# module.net
KiCad netlist of a schematic drawn in EAGLE
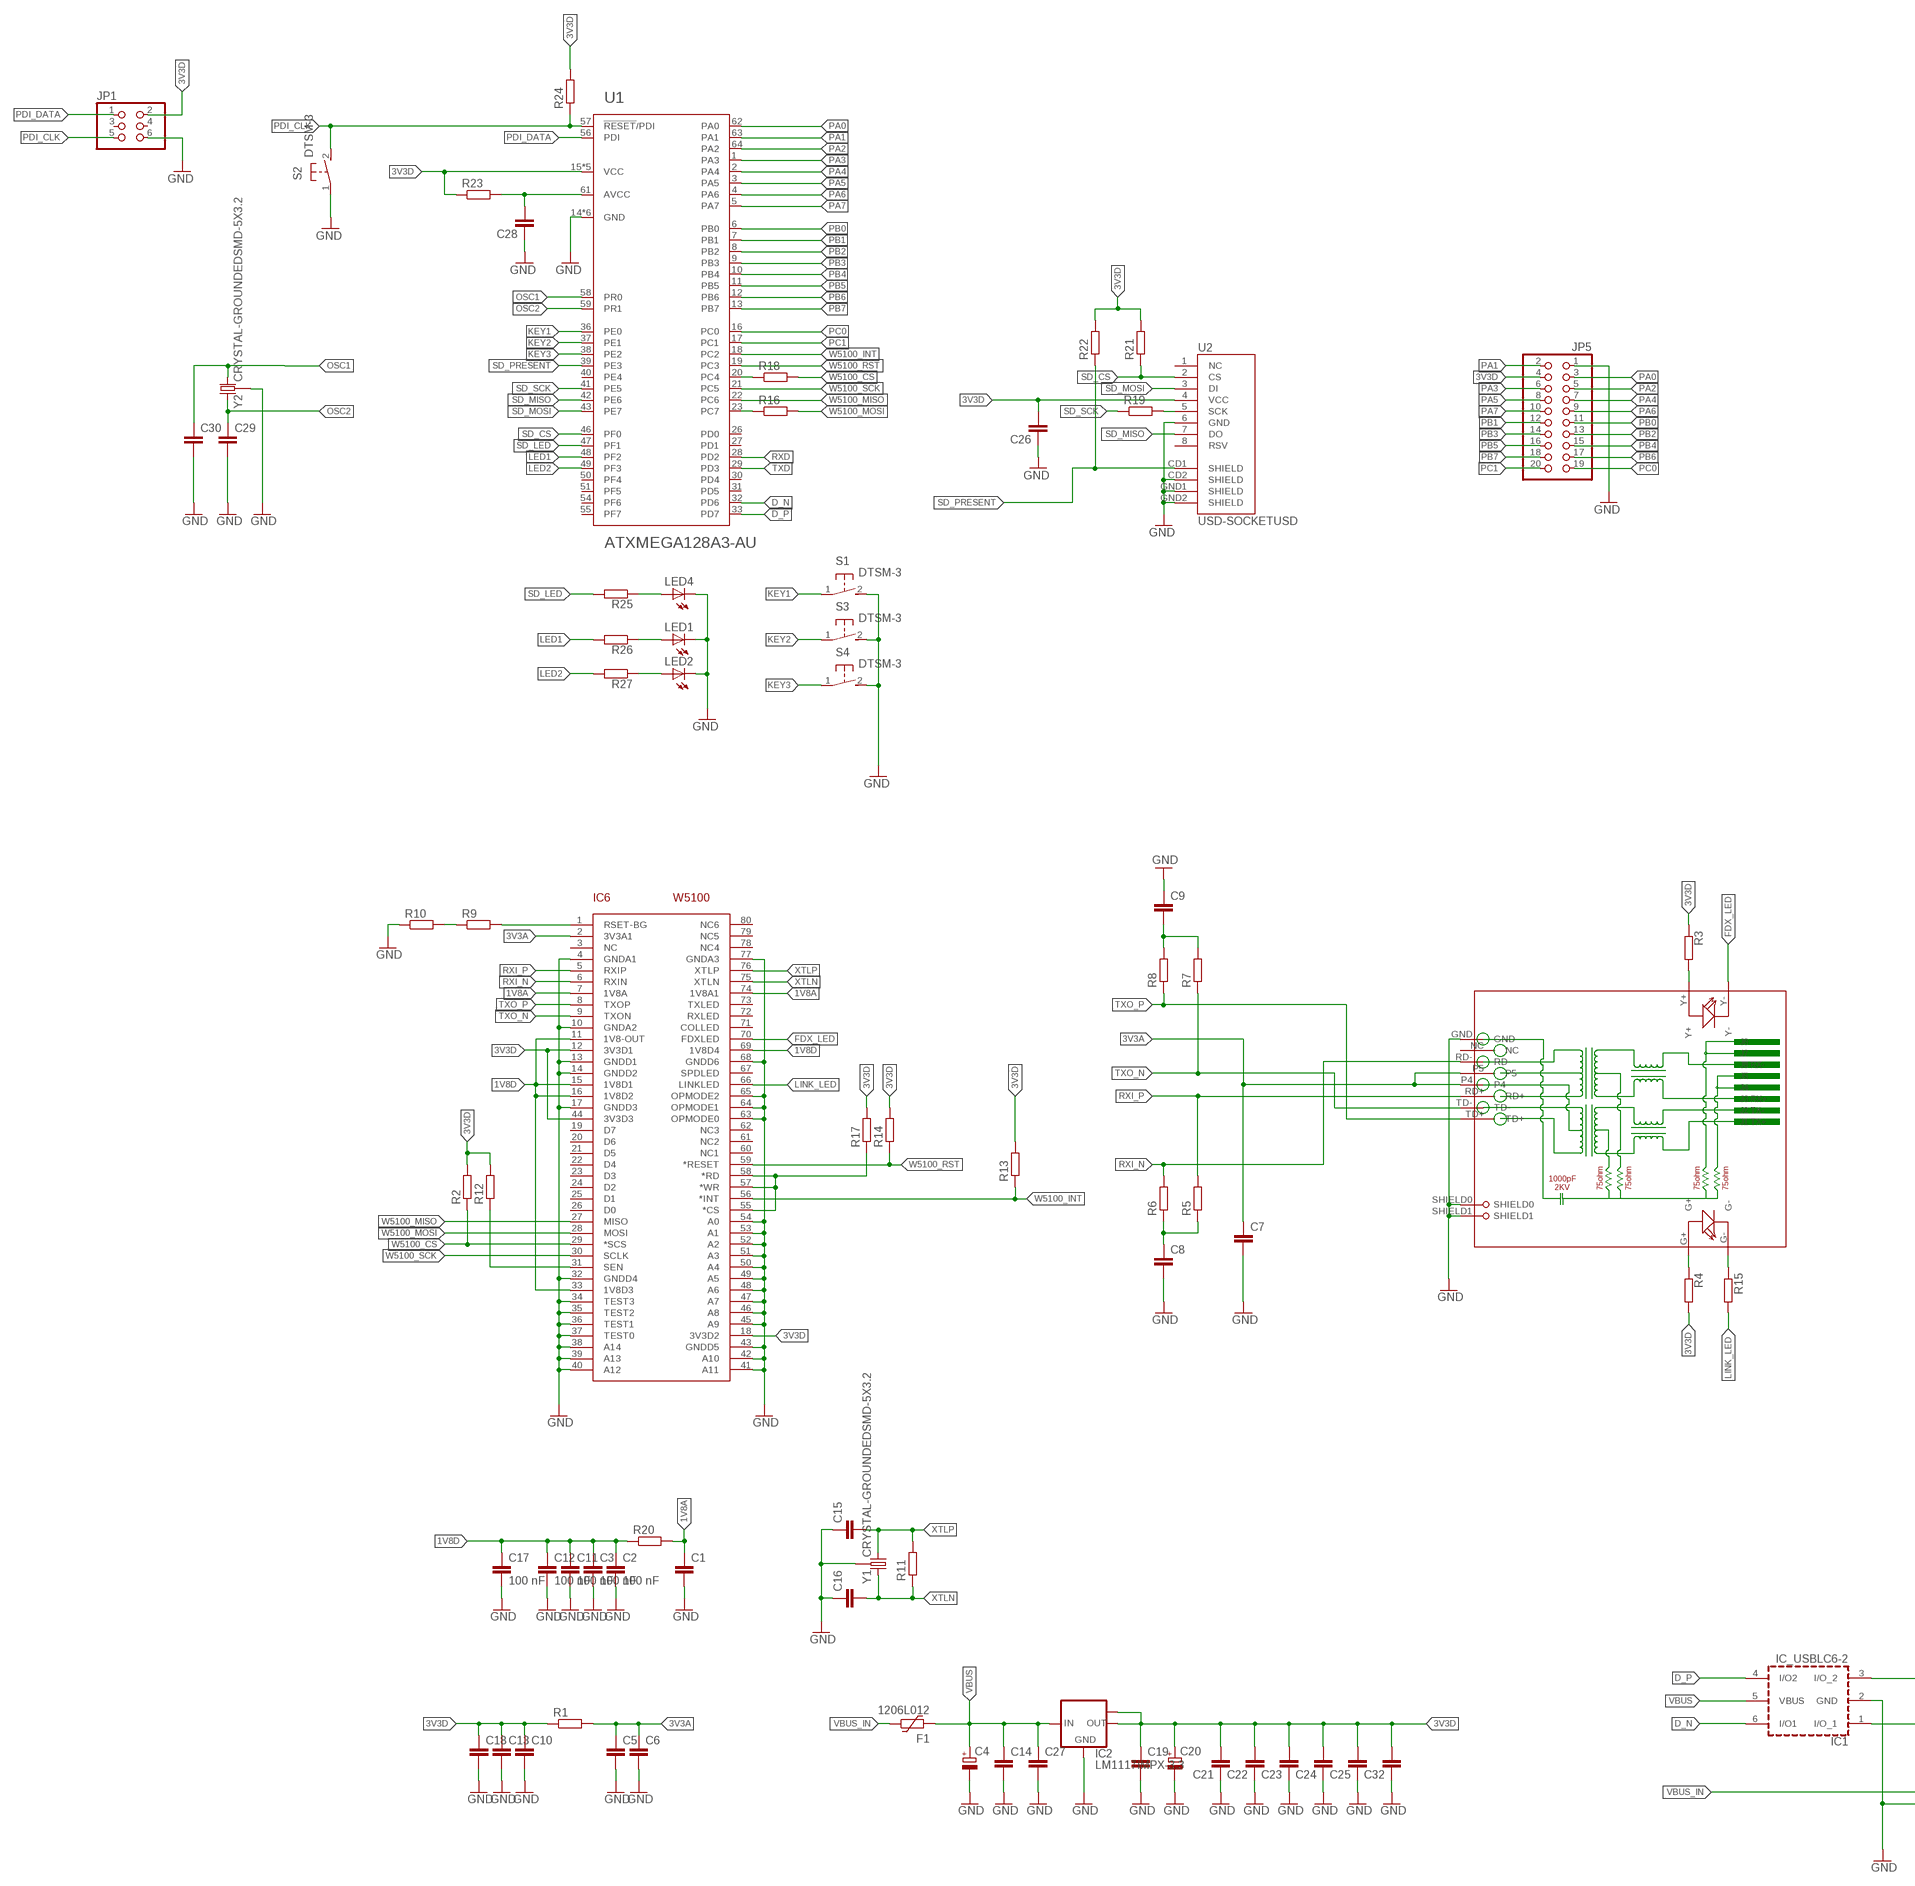
[diagram p0: schematic, sheet 1, part 1 of 2]
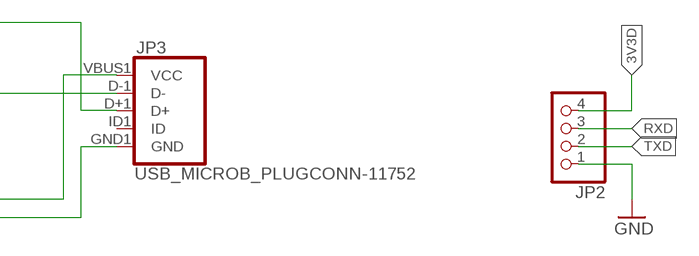
[diagram p1: schematic, sheet 1, part 2 of 2]

(export (version "E")
  (design (tool "Eeschema 10.0.6"))
  (components
    (comp (ref "C1")
      (value "C-EUC0603")
      (footprint "eagle-import:C0603")
      (libsource (lib "eagle-import") (part "C-EUC0603"))
    )
    (comp (ref "C2")
      (value "100 nF")
      (footprint "eagle-import:C0402")
      (libsource (lib "eagle-import") (part "C-EUC0402"))
    )
    (comp (ref "C3")
      (value "100 nF")
      (footprint "eagle-import:C0603")
      (libsource (lib "eagle-import") (part "C-EUC0603"))
    )
    (comp (ref "C4")
      (value "CPOL-EUSMCB")
      (footprint "eagle-import:SMC_B")
      (libsource (lib "eagle-import") (part "CPOL-EUSMCB"))
    )
    (comp (ref "C5")
      (value "C-EUC0603")
      (footprint "eagle-import:C0603")
      (libsource (lib "eagle-import") (part "C-EUC0603"))
    )
    (comp (ref "C6")
      (value "C-EUC0603")
      (footprint "eagle-import:C0603")
      (libsource (lib "eagle-import") (part "C-EUC0603"))
    )
    (comp (ref "C7")
      (value "C-EUC0603")
      (footprint "eagle-import:C0603")
      (libsource (lib "eagle-import") (part "C-EUC0603"))
    )
    (comp (ref "C8")
      (value "C-EUC0603")
      (footprint "eagle-import:C0603")
      (libsource (lib "eagle-import") (part "C-EUC0603"))
    )
    (comp (ref "C9")
      (value "C-EUC0603")
      (footprint "eagle-import:C0603")
      (libsource (lib "eagle-import") (part "C-EUC0603"))
    )
    (comp (ref "C10")
      (value "C-EUC0402")
      (footprint "eagle-import:C0402")
      (libsource (lib "eagle-import") (part "C-EUC0402"))
    )
    (comp (ref "C11")
      (value "100 nF")
      (footprint "eagle-import:C0402")
      (libsource (lib "eagle-import") (part "C-EUC0402"))
    )
    (comp (ref "C12")
      (value "100 nF")
      (footprint "eagle-import:C0402")
      (libsource (lib "eagle-import") (part "C-EUC0402"))
    )
    (comp (ref "C13")
      (value "C-EUC0402")
      (footprint "eagle-import:C0402")
      (libsource (lib "eagle-import") (part "C-EUC0402"))
    )
    (comp (ref "C14")
      (value "C-EUC0603")
      (footprint "eagle-import:C0603")
      (libsource (lib "eagle-import") (part "C-EUC0603"))
    )
    (comp (ref "C15")
      (value "C-EUC0603")
      (footprint "eagle-import:C0603")
      (libsource (lib "eagle-import") (part "C-EUC0603"))
    )
    (comp (ref "C16")
      (value "C-EUC0603")
      (footprint "eagle-import:C0603")
      (libsource (lib "eagle-import") (part "C-EUC0603"))
    )
    (comp (ref "C17")
      (value "100 nF")
      (footprint "eagle-import:C0402")
      (libsource (lib "eagle-import") (part "C-EUC0402"))
    )
    (comp (ref "C18")
      (value "C-EUC0402")
      (footprint "eagle-import:C0402")
      (libsource (lib "eagle-import") (part "C-EUC0402"))
    )
    (comp (ref "C19")
      (value "C-EUC0603")
      (footprint "eagle-import:C0603")
      (libsource (lib "eagle-import") (part "C-EUC0603"))
    )
    (comp (ref "C20")
      (value "CPOL-EUSMCB")
      (footprint "eagle-import:SMC_B")
      (libsource (lib "eagle-import") (part "CPOL-EUSMCB"))
    )
    (comp (ref "C21")
      (value "C-EUC0402")
      (footprint "eagle-import:C0402")
      (libsource (lib "eagle-import") (part "C-EUC0402"))
    )
    (comp (ref "C22")
      (value "C-EUC0402")
      (footprint "eagle-import:C0402")
      (libsource (lib "eagle-import") (part "C-EUC0402"))
    )
    (comp (ref "C23")
      (value "C-EUC0402")
      (footprint "eagle-import:C0402")
      (libsource (lib "eagle-import") (part "C-EUC0402"))
    )
    (comp (ref "C24")
      (value "C-EUC0402")
      (footprint "eagle-import:C0402")
      (libsource (lib "eagle-import") (part "C-EUC0402"))
    )
    (comp (ref "C25")
      (value "C-EUC0402")
      (footprint "eagle-import:C0402")
      (libsource (lib "eagle-import") (part "C-EUC0402"))
    )
    (comp (ref "C26")
      (value "C-EUC0603")
      (footprint "eagle-import:C0603")
      (libsource (lib "eagle-import") (part "C-EUC0603"))
    )
    (comp (ref "C27")
      (value "C-EUC0603")
      (footprint "eagle-import:C0603")
      (libsource (lib "eagle-import") (part "C-EUC0603"))
    )
    (comp (ref "C28")
      (value "C-EUC0402")
      (footprint "eagle-import:C0402")
      (libsource (lib "eagle-import") (part "C-EUC0402"))
    )
    (comp (ref "C29")
      (value "C-EUC0603")
      (footprint "eagle-import:C0603")
      (libsource (lib "eagle-import") (part "C-EUC0603"))
    )
    (comp (ref "C30")
      (value "C-EUC0603")
      (footprint "eagle-import:C0603")
      (libsource (lib "eagle-import") (part "C-EUC0603"))
    )
    (comp (ref "C32")
      (value "C-EUC0603")
      (footprint "eagle-import:C0603")
      (libsource (lib "eagle-import") (part "C-EUC0603"))
    )
    (comp (ref "F1")
      (value "1206L012")
      (footprint "eagle-import:1206L")
      (fields (field (name "MF") "Littelfuse"))
      (libsource (lib "eagle-import") (part "?1206L012"))
    )
    (comp (ref "IC1")
      (value "IC_USBLC6-2")
      (footprint "eagle-import:SOT-23-6L")
      (libsource (lib "eagle-import") (part "IC_USBLC6-2"))
    )
    (comp (ref "IC2")
      (value "LM1117IMPX-3.3")
      (footprint "eagle-import:SOT223")
      (libsource (lib "eagle-import") (part "LM1117IMPX-3.3"))
    )
    (comp (ref "IC6")
      (value "W5100")
      (footprint "eagle-import:SQFP-S-10X10-80")
      (libsource (lib "eagle-import") (part "W5100"))
    )
    (comp (ref "JP1")
      (value "PINHD-2X3")
      (footprint "eagle-import:2X03")
      (libsource (lib "eagle-import") (part "PINHD-2X3"))
    )
    (comp (ref "JP2")
      (value "PINHD-1X4")
      (footprint "eagle-import:1X04")
      (libsource (lib "eagle-import") (part "PINHD-1X4"))
    )
    (comp (ref "JP3")
      (value "USB_MICROB_PLUGCONN-11752")
      (footprint "eagle-import:USB-B-MICRO-SMD_V03")
      (libsource (lib "eagle-import") (part "USB_MICROB_PLUGCONN-11752"))
    )
    (comp (ref "JP5")
      (value "PINHD-2X10_2.54-SMD")
      (footprint "eagle-import:2X10SMD")
      (libsource (lib "eagle-import") (part "PINHD-2X10_2.54-SMD"))
    )
    (comp (ref "LED1")
      (value "LEDCHIPLED_0805")
      (footprint "eagle-import:CHIPLED_0805")
      (libsource (lib "eagle-import") (part "LEDCHIPLED_0805"))
    )
    (comp (ref "LED2")
      (value "LEDCHIPLED_0805")
      (footprint "eagle-import:CHIPLED_0805")
      (libsource (lib "eagle-import") (part "LEDCHIPLED_0805"))
    )
    (comp (ref "LED4")
      (value "LEDCHIPLED_0805")
      (footprint "eagle-import:CHIPLED_0805")
      (libsource (lib "eagle-import") (part "LEDCHIPLED_0805"))
    )
    (comp (ref "R1")
      (value "R-EU_R0805")
      (footprint "eagle-import:R0805")
      (libsource (lib "eagle-import") (part "R-EU_R0805"))
    )
    (comp (ref "R2")
      (value "R-EU_R0603")
      (footprint "eagle-import:R0603")
      (libsource (lib "eagle-import") (part "R-EU_R0603"))
    )
    (comp (ref "R3")
      (value "R-EU_R0603")
      (footprint "eagle-import:R0603")
      (libsource (lib "eagle-import") (part "R-EU_R0603"))
    )
    (comp (ref "R4")
      (value "R-EU_R0603")
      (footprint "eagle-import:R0603")
      (libsource (lib "eagle-import") (part "R-EU_R0603"))
    )
    (comp (ref "R5")
      (value "R-EU_R0603")
      (footprint "eagle-import:R0603")
      (libsource (lib "eagle-import") (part "R-EU_R0603"))
    )
    (comp (ref "R6")
      (value "R-EU_R0603")
      (footprint "eagle-import:R0603")
      (libsource (lib "eagle-import") (part "R-EU_R0603"))
    )
    (comp (ref "R7")
      (value "R-EU_R0603")
      (footprint "eagle-import:R0603")
      (libsource (lib "eagle-import") (part "R-EU_R0603"))
    )
    (comp (ref "R8")
      (value "R-EU_R0603")
      (footprint "eagle-import:R0603")
      (libsource (lib "eagle-import") (part "R-EU_R0603"))
    )
    (comp (ref "R9")
      (value "R-EU_R0603")
      (footprint "eagle-import:R0603")
      (libsource (lib "eagle-import") (part "R-EU_R0603"))
    )
    (comp (ref "R10")
      (value "R-EU_R0603")
      (footprint "eagle-import:R0603")
      (libsource (lib "eagle-import") (part "R-EU_R0603"))
    )
    (comp (ref "R11")
      (value "R-EU_R0603")
      (footprint "eagle-import:R0603")
      (libsource (lib "eagle-import") (part "R-EU_R0603"))
    )
    (comp (ref "R12")
      (value "R-EU_R0402")
      (footprint "eagle-import:R0402")
      (libsource (lib "eagle-import") (part "R-EU_R0402"))
    )
    (comp (ref "R13")
      (value "R-EU_R0603")
      (footprint "eagle-import:R0603")
      (libsource (lib "eagle-import") (part "R-EU_R0603"))
    )
    (comp (ref "R14")
      (value "R-EU_R0402")
      (footprint "eagle-import:R0402")
      (libsource (lib "eagle-import") (part "R-EU_R0402"))
    )
    (comp (ref "R15")
      (value "R-EU_R0603")
      (footprint "eagle-import:R0603")
      (libsource (lib "eagle-import") (part "R-EU_R0603"))
    )
    (comp (ref "R16")
      (value "R-EU_R0603")
      (footprint "eagle-import:R0603")
      (libsource (lib "eagle-import") (part "R-EU_R0603"))
    )
    (comp (ref "R17")
      (value "R-EU_R0603")
      (footprint "eagle-import:R0603")
      (libsource (lib "eagle-import") (part "R-EU_R0603"))
    )
    (comp (ref "R18")
      (value "R-EU_R0603")
      (footprint "eagle-import:R0603")
      (libsource (lib "eagle-import") (part "R-EU_R0603"))
    )
    (comp (ref "R19")
      (value "R-EU_R0603")
      (footprint "eagle-import:R0603")
      (libsource (lib "eagle-import") (part "R-EU_R0603"))
    )
    (comp (ref "R20")
      (value "R-EU_R0805")
      (footprint "eagle-import:R0805")
      (libsource (lib "eagle-import") (part "R-EU_R0805"))
    )
    (comp (ref "R21")
      (value "R-EU_R0603")
      (footprint "eagle-import:R0603")
      (libsource (lib "eagle-import") (part "R-EU_R0603"))
    )
    (comp (ref "R22")
      (value "R-EU_R0603")
      (footprint "eagle-import:R0603")
      (libsource (lib "eagle-import") (part "R-EU_R0603"))
    )
    (comp (ref "R23")
      (value "R-EU_R0805")
      (footprint "eagle-import:R0805")
      (libsource (lib "eagle-import") (part "R-EU_R0805"))
    )
    (comp (ref "R24")
      (value "R-EU_R0603")
      (footprint "eagle-import:R0603")
      (libsource (lib "eagle-import") (part "R-EU_R0603"))
    )
    (comp (ref "R25")
      (value "R-EU_R0603")
      (footprint "eagle-import:R0603")
      (libsource (lib "eagle-import") (part "R-EU_R0603"))
    )
    (comp (ref "R26")
      (value "R-EU_R0603")
      (footprint "eagle-import:R0603")
      (libsource (lib "eagle-import") (part "R-EU_R0603"))
    )
    (comp (ref "R27")
      (value "R-EU_R0603")
      (footprint "eagle-import:R0603")
      (libsource (lib "eagle-import") (part "R-EU_R0603"))
    )
    (comp (ref "RJ1")
      (value "HR911105A")
      (footprint "eagle-import:HR911105A")
      (libsource (lib "eagle-import") (part "HR911105A"))
    )
    (comp (ref "S1")
      (value "DTSM-3")
      (footprint "eagle-import:DTSM-3")
      (libsource (lib "eagle-import") (part "DTSM-3"))
    )
    (comp (ref "S2")
      (value "DTSM-3")
      (footprint "eagle-import:DTSM-3")
      (libsource (lib "eagle-import") (part "DTSM-3"))
    )
    (comp (ref "S3")
      (value "DTSM-3")
      (footprint "eagle-import:DTSM-3")
      (libsource (lib "eagle-import") (part "DTSM-3"))
    )
    (comp (ref "S4")
      (value "DTSM-3")
      (footprint "eagle-import:DTSM-3")
      (libsource (lib "eagle-import") (part "DTSM-3"))
    )
    (comp (ref "U1")
      (value "ATXMEGA128A3-AU")
      (footprint "eagle-import:TQFP-64A-64")
      (libsource (lib "eagle-import") (part "ATXMEGA128A3-AU"))
    )
    (comp (ref "U2")
      (value "USD-SOCKETUSD")
      (footprint "eagle-import:USD-SOCKET-PP")
      (libsource (lib "eagle-import") (part "USD-SOCKETUSD"))
    )
    (comp (ref "Y1")
      (value "CRYSTAL-GROUNDEDSMD-5X3.2")
      (footprint "eagle-import:CRYSTAL-SMD-5X3.2-4PAD")
      (libsource (lib "eagle-import") (part "CRYSTAL-GROUNDEDSMD-5X3.2"))
    )
    (comp (ref "Y2")
      (value "CRYSTAL-GROUNDEDSMD-5X3.2")
      (footprint "eagle-import:CRYSTAL-SMD-5X3.2-4PAD")
      (libsource (lib "eagle-import") (part "CRYSTAL-GROUNDEDSMD-5X3.2"))
    )
  )
  (nets
    (net (code "1") (name "1V8A") (class "Default")
      (node (ref "C1") (pin "1") (pinfunction "1_1") (pintype "passive"))
      (node (ref "IC6") (pin "7") (pinfunction "1V8A_7") (pintype "power_in"))
      (node (ref "IC6") (pin "74") (pinfunction "1V8A1_74") (pintype "power_in"))
      (node (ref "R20") (pin "2") (pinfunction "2_2") (pintype "passive"))
    )
    (net (code "2") (name "1V8D") (class "Default")
      (node (ref "C11") (pin "1") (pinfunction "1_1") (pintype "passive"))
      (node (ref "C12") (pin "1") (pinfunction "1_1") (pintype "passive"))
      (node (ref "C17") (pin "1") (pinfunction "1_1") (pintype "passive"))
      (node (ref "C2") (pin "1") (pinfunction "1_1") (pintype "passive"))
      (node (ref "C3") (pin "1") (pinfunction "1_1") (pintype "passive"))
      (node (ref "IC6") (pin "11") (pinfunction "1V8-OUT_11") (pintype "power_in"))
      (node (ref "IC6") (pin "15") (pinfunction "1V8D1_15") (pintype "power_in"))
      (node (ref "IC6") (pin "16") (pinfunction "1V8D2_16") (pintype "power_in"))
      (node (ref "IC6") (pin "33") (pinfunction "1V8D3_33") (pintype "power_in"))
      (node (ref "IC6") (pin "69") (pinfunction "1V8D4_69") (pintype "power_in"))
      (node (ref "R20") (pin "1") (pinfunction "1_1") (pintype "passive"))
    )
    (net (code "3") (name "3V3A") (class "Default")
      (node (ref "C5") (pin "1") (pinfunction "1_1") (pintype "passive"))
      (node (ref "C6") (pin "1") (pinfunction "1_1") (pintype "passive"))
      (node (ref "C7") (pin "1") (pinfunction "1_1") (pintype "passive"))
      (node (ref "IC6") (pin "2") (pinfunction "3V3A1_2") (pintype "power_in"))
      (node (ref "R1") (pin "2") (pinfunction "2_2") (pintype "passive"))
      (node (ref "RJ1") (pin "P4") (pinfunction "P4_P4") (pintype "bidirectional"))
      (node (ref "RJ1") (pin "P5") (pinfunction "P5_P5") (pintype "bidirectional"))
    )
    (net (code "4") (name "3V3D") (class "Default")
      (node (ref "C10") (pin "1") (pinfunction "1_1") (pintype "passive"))
      (node (ref "C13") (pin "1") (pinfunction "1_1") (pintype "passive"))
      (node (ref "C18") (pin "1") (pinfunction "1_1") (pintype "passive"))
      (node (ref "C19") (pin "1") (pinfunction "1_1") (pintype "passive"))
      (node (ref "C20") (pin "+") (pinfunction "+_+") (pintype "passive"))
      (node (ref "C21") (pin "2") (pinfunction "2_2") (pintype "passive"))
      (node (ref "C22") (pin "2") (pinfunction "2_2") (pintype "passive"))
      (node (ref "C23") (pin "2") (pinfunction "2_2") (pintype "passive"))
      (node (ref "C24") (pin "2") (pinfunction "2_2") (pintype "passive"))
      (node (ref "C25") (pin "2") (pinfunction "2_2") (pintype "passive"))
      (node (ref "C26") (pin "2") (pinfunction "2_2") (pintype "passive"))
      (node (ref "C32") (pin "2") (pinfunction "2_2") (pintype "passive"))
      (node (ref "IC2") (pin "2") (pinfunction "OUT_2") (pintype "passive"))
      (node (ref "IC2") (pin "TAB") (pinfunction "OUT1_TAB") (pintype "passive"))
      (node (ref "IC6") (pin "12") (pinfunction "3V3D1_12") (pintype "power_in"))
      (node (ref "IC6") (pin "18") (pinfunction "3V3D2_18") (pintype "power_in"))
      (node (ref "IC6") (pin "44") (pinfunction "3V3D3_44") (pintype "power_in"))
      (node (ref "JP1") (pin "2") (pinfunction "2_2") (pintype "passive"))
      (node (ref "JP2") (pin "4") (pinfunction "4_4") (pintype "passive"))
      (node (ref "JP5") (pin "4") (pinfunction "4_4") (pintype "passive"))
      (node (ref "R1") (pin "1") (pinfunction "1_1") (pintype "passive"))
      (node (ref "R12") (pin "2") (pinfunction "2_2") (pintype "passive"))
      (node (ref "R13") (pin "2") (pinfunction "2_2") (pintype "passive"))
      (node (ref "R14") (pin "2") (pinfunction "2_2") (pintype "passive"))
      (node (ref "R17") (pin "2") (pinfunction "2_2") (pintype "passive"))
      (node (ref "R2") (pin "2") (pinfunction "2_2") (pintype "passive"))
      (node (ref "R21") (pin "2") (pinfunction "2_2") (pintype "passive"))
      (node (ref "R22") (pin "2") (pinfunction "2_2") (pintype "passive"))
      (node (ref "R23") (pin "1") (pinfunction "1_1") (pintype "passive"))
      (node (ref "R24") (pin "2") (pinfunction "2_2") (pintype "passive"))
      (node (ref "R3") (pin "1") (pinfunction "1_1") (pintype "passive"))
      (node (ref "R4") (pin "2") (pinfunction "2_2") (pintype "passive"))
      (node (ref "U1") (pin "15") (pinfunction "VCC_15") (pintype "power_in"))
      (node (ref "U1") (pin "25") (pinfunction "VCC_25") (pintype "power_in"))
      (node (ref "U1") (pin "35") (pinfunction "VCC_35") (pintype "power_in"))
      (node (ref "U1") (pin "45") (pinfunction "VCC_45") (pintype "power_in"))
      (node (ref "U1") (pin "53") (pinfunction "VCC_53") (pintype "power_in"))
      (node (ref "U2") (pin "4") (pinfunction "VCC_4") (pintype "bidirectional"))
    )
    (net (code "5") (name "D_N") (class "Default")
      (node (ref "IC1") (pin "6") (pinfunction "I/O1_6") (pintype "bidirectional"))
      (node (ref "U1") (pin "32") (pinfunction "PD6_32") (pintype "bidirectional"))
    )
    (net (code "6") (name "D_P") (class "Default")
      (node (ref "IC1") (pin "4") (pinfunction "I/O2_4") (pintype "bidirectional"))
      (node (ref "U1") (pin "33") (pinfunction "PD7_33") (pintype "bidirectional"))
    )
    (net (code "7") (name "FDX_LED") (class "Default")
      (node (ref "IC6") (pin "70") (pinfunction "FDXLED_70") (pintype "output"))
      (node (ref "RJ1") (pin "Y-") (pinfunction "Y-_Y-") (pintype "bidirectional"))
    )
    (net (code "8") (name "GND") (class "Default")
      (node (ref "C1") (pin "2") (pinfunction "2_2") (pintype "passive"))
      (node (ref "C10") (pin "2") (pinfunction "2_2") (pintype "passive"))
      (node (ref "C11") (pin "2") (pinfunction "2_2") (pintype "passive"))
      (node (ref "C12") (pin "2") (pinfunction "2_2") (pintype "passive"))
      (node (ref "C13") (pin "2") (pinfunction "2_2") (pintype "passive"))
      (node (ref "C14") (pin "2") (pinfunction "2_2") (pintype "passive"))
      (node (ref "C15") (pin "1") (pinfunction "1_1") (pintype "passive"))
      (node (ref "C16") (pin "1") (pinfunction "1_1") (pintype "passive"))
      (node (ref "C17") (pin "2") (pinfunction "2_2") (pintype "passive"))
      (node (ref "C18") (pin "2") (pinfunction "2_2") (pintype "passive"))
      (node (ref "C19") (pin "2") (pinfunction "2_2") (pintype "passive"))
      (node (ref "C2") (pin "2") (pinfunction "2_2") (pintype "passive"))
      (node (ref "C20") (pin "-") (pinfunction "-_-") (pintype "passive"))
      (node (ref "C21") (pin "1") (pinfunction "1_1") (pintype "passive"))
      (node (ref "C22") (pin "1") (pinfunction "1_1") (pintype "passive"))
      (node (ref "C23") (pin "1") (pinfunction "1_1") (pintype "passive"))
      (node (ref "C24") (pin "1") (pinfunction "1_1") (pintype "passive"))
      (node (ref "C25") (pin "1") (pinfunction "1_1") (pintype "passive"))
      (node (ref "C26") (pin "1") (pinfunction "1_1") (pintype "passive"))
      (node (ref "C27") (pin "2") (pinfunction "2_2") (pintype "passive"))
      (node (ref "C28") (pin "1") (pinfunction "1_1") (pintype "passive"))
      (node (ref "C29") (pin "2") (pinfunction "2_2") (pintype "passive"))
      (node (ref "C3") (pin "2") (pinfunction "2_2") (pintype "passive"))
      (node (ref "C30") (pin "2") (pinfunction "2_2") (pintype "passive"))
      (node (ref "C32") (pin "1") (pinfunction "1_1") (pintype "passive"))
      (node (ref "C4") (pin "-") (pinfunction "-_-") (pintype "passive"))
      (node (ref "C5") (pin "2") (pinfunction "2_2") (pintype "passive"))
      (node (ref "C6") (pin "2") (pinfunction "2_2") (pintype "passive"))
      (node (ref "C7") (pin "2") (pinfunction "2_2") (pintype "passive"))
      (node (ref "C8") (pin "2") (pinfunction "2_2") (pintype "passive"))
      (node (ref "C9") (pin "1") (pinfunction "1_1") (pintype "passive"))
      (node (ref "IC1") (pin "2") (pinfunction "GND_2") (pintype "bidirectional"))
      (node (ref "IC2") (pin "1") (pinfunction "GND_1") (pintype "input"))
      (node (ref "IC6") (pin "10") (pinfunction "GNDA2_10") (pintype "power_in"))
      (node (ref "IC6") (pin "13") (pinfunction "GNDD1_13") (pintype "power_in"))
      (node (ref "IC6") (pin "14") (pinfunction "GNDD2_14") (pintype "power_in"))
      (node (ref "IC6") (pin "17") (pinfunction "GNDD3_17") (pintype "power_in"))
      (node (ref "IC6") (pin "32") (pinfunction "GNDD4_32") (pintype "power_in"))
      (node (ref "IC6") (pin "34") (pinfunction "TEST3_34") (pintype "input"))
      (node (ref "IC6") (pin "35") (pinfunction "TEST2_35") (pintype "input"))
      (node (ref "IC6") (pin "36") (pinfunction "TEST1_36") (pintype "input"))
      (node (ref "IC6") (pin "37") (pinfunction "TEST0_37") (pintype "input"))
      (node (ref "IC6") (pin "38") (pinfunction "A14_38") (pintype "input"))
      (node (ref "IC6") (pin "39") (pinfunction "A13_39") (pintype "input"))
      (node (ref "IC6") (pin "4") (pinfunction "GNDA1_4") (pintype "power_in"))
      (node (ref "IC6") (pin "40") (pinfunction "A12_40") (pintype "input"))
      (node (ref "IC6") (pin "41") (pinfunction "A11_41") (pintype "input"))
      (node (ref "IC6") (pin "42") (pinfunction "A10_42") (pintype "input"))
      (node (ref "IC6") (pin "43") (pinfunction "GNDD5_43") (pintype "power_in"))
      (node (ref "IC6") (pin "45") (pinfunction "A9_45") (pintype "input"))
      (node (ref "IC6") (pin "46") (pinfunction "A8_46") (pintype "input"))
      (node (ref "IC6") (pin "47") (pinfunction "A7_47") (pintype "input"))
      (node (ref "IC6") (pin "48") (pinfunction "A6_48") (pintype "input"))
      (node (ref "IC6") (pin "49") (pinfunction "A5_49") (pintype "input"))
      (node (ref "IC6") (pin "50") (pinfunction "A4_50") (pintype "input"))
      (node (ref "IC6") (pin "51") (pinfunction "A3_51") (pintype "input"))
      (node (ref "IC6") (pin "52") (pinfunction "A2_52") (pintype "input"))
      (node (ref "IC6") (pin "53") (pinfunction "A1_53") (pintype "input"))
      (node (ref "IC6") (pin "54") (pinfunction "A0_54") (pintype "input"))
      (node (ref "IC6") (pin "63") (pinfunction "OPMODE0_63") (pintype "input"))
      (node (ref "IC6") (pin "64") (pinfunction "OPMODE1_64") (pintype "input"))
      (node (ref "IC6") (pin "65") (pinfunction "OPMODE2_65") (pintype "input"))
      (node (ref "IC6") (pin "68") (pinfunction "GNDD6_68") (pintype "power_in"))
      (node (ref "IC6") (pin "77") (pinfunction "GNDA3_77") (pintype "power_in"))
      (node (ref "JP1") (pin "6") (pinfunction "6_6") (pintype "passive"))
      (node (ref "JP2") (pin "1") (pinfunction "1_1") (pintype "passive"))
      (node (ref "JP3") (pin "GND1") (pinfunction "GND_GND1") (pintype "bidirectional"))
      (node (ref "JP5") (pin "1") (pinfunction "1_1") (pintype "passive"))
      (node (ref "LED1") (pin "C") (pinfunction "C_C") (pintype "passive"))
      (node (ref "LED2") (pin "C") (pinfunction "C_C") (pintype "passive"))
      (node (ref "LED4") (pin "C") (pinfunction "C_C") (pintype "passive"))
      (node (ref "R10") (pin "1") (pinfunction "1_1") (pintype "passive"))
      (node (ref "RJ1") (pin "GND") (pinfunction "GND_GND") (pintype "bidirectional"))
      (node (ref "RJ1") (pin "SHIELD0") (pinfunction "SHIELD0_SHIELD0") (pintype "bidirectional"))
      (node (ref "RJ1") (pin "SHIELD1") (pinfunction "SHIELD1_SHIELD1") (pintype "bidirectional"))
      (node (ref "S1") (pin "2") (pinfunction "2_2") (pintype "passive"))
      (node (ref "S2") (pin "1") (pinfunction "1_1") (pintype "passive"))
      (node (ref "S3") (pin "2") (pinfunction "2_2") (pintype "passive"))
      (node (ref "S4") (pin "2") (pinfunction "2_2") (pintype "passive"))
      (node (ref "U1") (pin "14") (pinfunction "GND_14") (pintype "power_in"))
      (node (ref "U1") (pin "24") (pinfunction "GND_24") (pintype "power_in"))
      (node (ref "U1") (pin "34") (pinfunction "GND_34") (pintype "power_in"))
      (node (ref "U1") (pin "44") (pinfunction "GND_44") (pintype "power_in"))
      (node (ref "U1") (pin "52") (pinfunction "GND_52") (pintype "power_in"))
      (node (ref "U1") (pin "60") (pinfunction "GND_60") (pintype "power_in"))
      (node (ref "U2") (pin "6") (pinfunction "GND_6") (pintype "bidirectional"))
      (node (ref "U2") (pin "CD2") (pinfunction "SHIELD_CD2") (pintype "bidirectional"))
      (node (ref "U2") (pin "GND1") (pinfunction "SHIELD_GND1") (pintype "bidirectional"))
      (node (ref "U2") (pin "GND2") (pinfunction "SHIELD_GND2") (pintype "bidirectional"))
      (node (ref "Y1") (pin "2") (pinfunction "3_2") (pintype "passive"))
      (node (ref "Y1") (pin "4") (pinfunction "3_4") (pintype "passive"))
      (node (ref "Y2") (pin "2") (pinfunction "3_2") (pintype "passive"))
      (node (ref "Y2") (pin "4") (pinfunction "3_4") (pintype "passive"))
    )
    (net (code "9") (name "KEY1") (class "Default")
      (node (ref "S1") (pin "1") (pinfunction "1_1") (pintype "passive"))
      (node (ref "U1") (pin "36") (pinfunction "PE0_36") (pintype "bidirectional"))
    )
    (net (code "10") (name "KEY2") (class "Default")
      (node (ref "S3") (pin "1") (pinfunction "1_1") (pintype "passive"))
      (node (ref "U1") (pin "37") (pinfunction "PE1_37") (pintype "bidirectional"))
    )
    (net (code "11") (name "KEY3") (class "Default")
      (node (ref "S4") (pin "1") (pinfunction "1_1") (pintype "passive"))
      (node (ref "U1") (pin "38") (pinfunction "PE2_38") (pintype "bidirectional"))
    )
    (net (code "12") (name "LED1") (class "Default")
      (node (ref "R26") (pin "2") (pinfunction "2_2") (pintype "passive"))
      (node (ref "U1") (pin "48") (pinfunction "PF2_48") (pintype "bidirectional"))
    )
    (net (code "13") (name "LED2") (class "Default")
      (node (ref "R27") (pin "2") (pinfunction "2_2") (pintype "passive"))
      (node (ref "U1") (pin "49") (pinfunction "PF3_49") (pintype "bidirectional"))
    )
    (net (code "14") (name "LINK_LED") (class "Default")
      (node (ref "IC6") (pin "66") (pinfunction "LINKLED_66") (pintype "output"))
      (node (ref "R15") (pin "2") (pinfunction "2_2") (pintype "passive"))
    )
    (net (code "15") (name "Net-(C8-Pad1)") (class "Default")
      (node (ref "C8") (pin "1") (pinfunction "1_1") (pintype "passive"))
      (node (ref "R5") (pin "1") (pinfunction "1_1") (pintype "passive"))
      (node (ref "R6") (pin "1") (pinfunction "1_1") (pintype "passive"))
    )
    (net (code "16") (name "Net-(C9-Pad2)") (class "Default")
      (node (ref "C9") (pin "2") (pinfunction "2_2") (pintype "passive"))
      (node (ref "R7") (pin "2") (pinfunction "2_2") (pintype "passive"))
      (node (ref "R8") (pin "2") (pinfunction "2_2") (pintype "passive"))
    )
    (net (code "17") (name "Net-(IC1-I{slash}O_1)") (class "Default")
      (node (ref "IC1") (pin "1") (pinfunction "I/O_1_1") (pintype "bidirectional"))
      (node (ref "JP3") (pin "D-1") (pinfunction "D-_D-1") (pintype "bidirectional"))
    )
    (net (code "18") (name "Net-(IC1-I{slash}O_2)") (class "Default")
      (node (ref "IC1") (pin "3") (pinfunction "I/O_2_3") (pintype "bidirectional"))
      (node (ref "JP3") (pin "D+1") (pinfunction "D+_D+1") (pintype "bidirectional"))
    )
    (net (code "19") (name "Net-(IC6-*CS)") (class "Default")
      (node (ref "IC6") (pin "55") (pinfunction "*CS_55") (pintype "input"))
      (node (ref "IC6") (pin "57") (pinfunction "*WR_57") (pintype "input"))
      (node (ref "IC6") (pin "58") (pinfunction "*RD_58") (pintype "input"))
      (node (ref "R17") (pin "1") (pinfunction "1_1") (pintype "passive"))
    )
    (net (code "20") (name "Net-(IC6-RSET-BG)") (class "Default")
      (node (ref "IC6") (pin "1") (pinfunction "RSET-BG_1") (pintype "input"))
      (node (ref "R9") (pin "2") (pinfunction "2_2") (pintype "passive"))
    )
    (net (code "21") (name "Net-(IC6-SEN)") (class "Default")
      (node (ref "IC6") (pin "31") (pinfunction "SEN_31") (pintype "input"))
      (node (ref "R12") (pin "1") (pinfunction "1_1") (pintype "passive"))
    )
    (net (code "22") (name "Net-(LED1-PadA)") (class "Default")
      (node (ref "LED1") (pin "A") (pinfunction "A_A") (pintype "passive"))
      (node (ref "R26") (pin "1") (pinfunction "1_1") (pintype "passive"))
    )
    (net (code "23") (name "Net-(LED2-PadA)") (class "Default")
      (node (ref "LED2") (pin "A") (pinfunction "A_A") (pintype "passive"))
      (node (ref "R27") (pin "1") (pinfunction "1_1") (pintype "passive"))
    )
    (net (code "24") (name "Net-(LED4-PadA)") (class "Default")
      (node (ref "LED4") (pin "A") (pinfunction "A_A") (pintype "passive"))
      (node (ref "R25") (pin "1") (pinfunction "1_1") (pintype "passive"))
    )
    (net (code "25") (name "Net-(R3-Pad2)") (class "Default")
      (node (ref "R3") (pin "2") (pinfunction "2_2") (pintype "passive"))
      (node (ref "RJ1") (pin "Y+") (pinfunction "Y+_Y+") (pintype "bidirectional"))
    )
    (net (code "26") (name "Net-(R4-Pad1)") (class "Default")
      (node (ref "R4") (pin "1") (pinfunction "1_1") (pintype "passive"))
      (node (ref "RJ1") (pin "G+") (pinfunction "G+_G+") (pintype "bidirectional"))
    )
    (net (code "27") (name "Net-(R10-Pad2)") (class "Default")
      (node (ref "R10") (pin "2") (pinfunction "2_2") (pintype "passive"))
      (node (ref "R9") (pin "1") (pinfunction "1_1") (pintype "passive"))
    )
    (net (code "28") (name "Net-(R15-Pad1)") (class "Default")
      (node (ref "R15") (pin "1") (pinfunction "1_1") (pintype "passive"))
      (node (ref "RJ1") (pin "G-") (pinfunction "G-_G-") (pintype "bidirectional"))
    )
    (net (code "29") (name "Net-(U1-AVCC)") (class "Default")
      (node (ref "C28") (pin "2") (pinfunction "2_2") (pintype "passive"))
      (node (ref "R23") (pin "2") (pinfunction "2_2") (pintype "passive"))
      (node (ref "U1") (pin "61") (pinfunction "AVCC_61") (pintype "power_in"))
    )
    (net (code "30") (name "Net-(U1-PC4)") (class "Default")
      (node (ref "R18") (pin "1") (pinfunction "1_1") (pintype "passive"))
      (node (ref "U1") (pin "20") (pinfunction "PC4_20") (pintype "bidirectional"))
    )
    (net (code "31") (name "Net-(U1-PC7)") (class "Default")
      (node (ref "R16") (pin "1") (pinfunction "1_1") (pintype "passive"))
      (node (ref "U1") (pin "23") (pinfunction "PC7_23") (pintype "bidirectional"))
    )
    (net (code "32") (name "Net-(U2-SCK)") (class "Default")
      (node (ref "R19") (pin "2") (pinfunction "2_2") (pintype "passive"))
      (node (ref "U2") (pin "5") (pinfunction "SCK_5") (pintype "bidirectional"))
    )
    (net (code "33") (name "OSC1") (class "Default")
      (node (ref "C30") (pin "1") (pinfunction "1_1") (pintype "passive"))
      (node (ref "U1") (pin "58") (pinfunction "PR0_58") (pintype "bidirectional"))
      (node (ref "Y2") (pin "1") (pinfunction "2_1") (pintype "passive"))
    )
    (net (code "34") (name "OSC2") (class "Default")
      (node (ref "C29") (pin "1") (pinfunction "1_1") (pintype "passive"))
      (node (ref "U1") (pin "59") (pinfunction "PR1_59") (pintype "bidirectional"))
      (node (ref "Y2") (pin "3") (pinfunction "1_3") (pintype "passive"))
    )
    (net (code "35") (name "PA0") (class "Default")
      (node (ref "JP5") (pin "3") (pinfunction "3_3") (pintype "passive"))
      (node (ref "U1") (pin "62") (pinfunction "PA0_62") (pintype "bidirectional"))
    )
    (net (code "36") (name "PA1") (class "Default")
      (node (ref "JP5") (pin "2") (pinfunction "2_2") (pintype "passive"))
      (node (ref "U1") (pin "63") (pinfunction "PA1_63") (pintype "bidirectional"))
    )
    (net (code "37") (name "PA2") (class "Default")
      (node (ref "JP5") (pin "5") (pinfunction "5_5") (pintype "passive"))
      (node (ref "U1") (pin "64") (pinfunction "PA2_64") (pintype "bidirectional"))
    )
    (net (code "38") (name "PA3") (class "Default")
      (node (ref "JP5") (pin "6") (pinfunction "6_6") (pintype "passive"))
      (node (ref "U1") (pin "1") (pinfunction "PA3_1") (pintype "bidirectional"))
    )
    (net (code "39") (name "PA4") (class "Default")
      (node (ref "JP5") (pin "7") (pinfunction "7_7") (pintype "passive"))
      (node (ref "U1") (pin "2") (pinfunction "PA4_2") (pintype "bidirectional"))
    )
    (net (code "40") (name "PA5") (class "Default")
      (node (ref "JP5") (pin "8") (pinfunction "8_8") (pintype "passive"))
      (node (ref "U1") (pin "3") (pinfunction "PA5_3") (pintype "bidirectional"))
    )
    (net (code "41") (name "PA6") (class "Default")
      (node (ref "JP5") (pin "9") (pinfunction "9_9") (pintype "passive"))
      (node (ref "U1") (pin "4") (pinfunction "PA6_4") (pintype "bidirectional"))
    )
    (net (code "42") (name "PA7") (class "Default")
      (node (ref "JP5") (pin "10") (pinfunction "10_10") (pintype "passive"))
      (node (ref "U1") (pin "5") (pinfunction "PA7_5") (pintype "bidirectional"))
    )
    (net (code "43") (name "PB0") (class "Default")
      (node (ref "JP5") (pin "11") (pinfunction "11_11") (pintype "passive"))
      (node (ref "U1") (pin "6") (pinfunction "PB0_6") (pintype "bidirectional"))
    )
    (net (code "44") (name "PB1") (class "Default")
      (node (ref "JP5") (pin "12") (pinfunction "12_12") (pintype "passive"))
      (node (ref "U1") (pin "7") (pinfunction "PB1_7") (pintype "bidirectional"))
    )
    (net (code "45") (name "PB2") (class "Default")
      (node (ref "JP5") (pin "13") (pinfunction "13_13") (pintype "passive"))
      (node (ref "U1") (pin "8") (pinfunction "PB2_8") (pintype "bidirectional"))
    )
    (net (code "46") (name "PB3") (class "Default")
      (node (ref "JP5") (pin "14") (pinfunction "14_14") (pintype "passive"))
      (node (ref "U1") (pin "9") (pinfunction "PB3_9") (pintype "bidirectional"))
    )
    (net (code "47") (name "PB4") (class "Default")
      (node (ref "JP5") (pin "15") (pinfunction "15_15") (pintype "passive"))
      (node (ref "U1") (pin "10") (pinfunction "PB4_10") (pintype "bidirectional"))
    )
    (net (code "48") (name "PB5") (class "Default")
      (node (ref "JP5") (pin "16") (pinfunction "16_16") (pintype "passive"))
      (node (ref "U1") (pin "11") (pinfunction "PB5_11") (pintype "bidirectional"))
    )
    (net (code "49") (name "PB6") (class "Default")
      (node (ref "JP5") (pin "17") (pinfunction "17_17") (pintype "passive"))
      (node (ref "U1") (pin "12") (pinfunction "PB6_12") (pintype "bidirectional"))
    )
    (net (code "50") (name "PB7") (class "Default")
      (node (ref "JP5") (pin "18") (pinfunction "18_18") (pintype "passive"))
      (node (ref "U1") (pin "13") (pinfunction "PB7_13") (pintype "bidirectional"))
    )
    (net (code "51") (name "PC0") (class "Default")
      (node (ref "JP5") (pin "19") (pinfunction "19_19") (pintype "passive"))
      (node (ref "U1") (pin "16") (pinfunction "PC0_16") (pintype "bidirectional"))
    )
    (net (code "52") (name "PC1") (class "Default")
      (node (ref "JP5") (pin "20") (pinfunction "20_20") (pintype "passive"))
      (node (ref "U1") (pin "17") (pinfunction "PC1_17") (pintype "bidirectional"))
    )
    (net (code "53") (name "PDI_CLK") (class "Default")
      (node (ref "JP1") (pin "5") (pinfunction "5_5") (pintype "passive"))
      (node (ref "R24") (pin "1") (pinfunction "1_1") (pintype "passive"))
      (node (ref "S2") (pin "2") (pinfunction "2_2") (pintype "passive"))
      (node (ref "U1") (pin "57") (pinfunction "~{RESET}/PDI_57") (pintype "bidirectional"))
    )
    (net (code "54") (name "PDI_DATA") (class "Default")
      (node (ref "JP1") (pin "1") (pinfunction "1_1") (pintype "passive"))
      (node (ref "U1") (pin "56") (pinfunction "PDI_56") (pintype "bidirectional"))
    )
    (net (code "55") (name "RXD") (class "Default")
      (node (ref "JP2") (pin "3") (pinfunction "3_3") (pintype "passive"))
      (node (ref "U1") (pin "28") (pinfunction "PD2_28") (pintype "bidirectional"))
    )
    (net (code "56") (name "RXI_N") (class "Default")
      (node (ref "IC6") (pin "6") (pinfunction "RXIN_6") (pintype "input"))
      (node (ref "R6") (pin "2") (pinfunction "2_2") (pintype "passive"))
      (node (ref "RJ1") (pin "RD-") (pinfunction "RD-_RD-") (pintype "bidirectional"))
    )
    (net (code "57") (name "RXI_P") (class "Default")
      (node (ref "IC6") (pin "5") (pinfunction "RXIP_5") (pintype "input"))
      (node (ref "R5") (pin "2") (pinfunction "2_2") (pintype "passive"))
      (node (ref "RJ1") (pin "RD+") (pinfunction "RD+_RD+") (pintype "bidirectional"))
    )
    (net (code "58") (name "SD_CS") (class "Default")
      (node (ref "R21") (pin "1") (pinfunction "1_1") (pintype "passive"))
      (node (ref "U1") (pin "46") (pinfunction "PF0_46") (pintype "bidirectional"))
      (node (ref "U2") (pin "2") (pinfunction "CS_2") (pintype "bidirectional"))
    )
    (net (code "59") (name "SD_LED") (class "Default")
      (node (ref "R25") (pin "2") (pinfunction "2_2") (pintype "passive"))
      (node (ref "U1") (pin "47") (pinfunction "PF1_47") (pintype "bidirectional"))
    )
    (net (code "60") (name "SD_MISO") (class "Default")
      (node (ref "U1") (pin "42") (pinfunction "PE6_42") (pintype "bidirectional"))
      (node (ref "U2") (pin "7") (pinfunction "DO_7") (pintype "bidirectional"))
    )
    (net (code "61") (name "SD_MOSI") (class "Default")
      (node (ref "U1") (pin "43") (pinfunction "PE7_43") (pintype "bidirectional"))
      (node (ref "U2") (pin "3") (pinfunction "DI_3") (pintype "bidirectional"))
    )
    (net (code "62") (name "SD_PRESENT") (class "Default")
      (node (ref "R22") (pin "1") (pinfunction "1_1") (pintype "passive"))
      (node (ref "U1") (pin "39") (pinfunction "PE3_39") (pintype "bidirectional"))
      (node (ref "U2") (pin "CD1") (pinfunction "SHIELD_CD1") (pintype "bidirectional"))
    )
    (net (code "63") (name "SD_SCK") (class "Default")
      (node (ref "R19") (pin "1") (pinfunction "1_1") (pintype "passive"))
      (node (ref "U1") (pin "41") (pinfunction "PE5_41") (pintype "bidirectional"))
    )
    (net (code "64") (name "TXD") (class "Default")
      (node (ref "JP2") (pin "2") (pinfunction "2_2") (pintype "passive"))
      (node (ref "U1") (pin "29") (pinfunction "PD3_29") (pintype "bidirectional"))
    )
    (net (code "65") (name "TXO_N") (class "Default")
      (node (ref "IC6") (pin "9") (pinfunction "TXON_9") (pintype "output"))
      (node (ref "R7") (pin "1") (pinfunction "1_1") (pintype "passive"))
      (node (ref "RJ1") (pin "TD-") (pinfunction "TD-_TD-") (pintype "bidirectional"))
    )
    (net (code "66") (name "TXO_P") (class "Default")
      (node (ref "IC6") (pin "8") (pinfunction "TXOP_8") (pintype "output"))
      (node (ref "R8") (pin "1") (pinfunction "1_1") (pintype "passive"))
      (node (ref "RJ1") (pin "TD+") (pinfunction "TD+_TD+") (pintype "bidirectional"))
    )
    (net (code "67") (name "VBUS") (class "Default")
      (node (ref "C14") (pin "1") (pinfunction "1_1") (pintype "passive"))
      (node (ref "C27") (pin "1") (pinfunction "1_1") (pintype "passive"))
      (node (ref "C4") (pin "+") (pinfunction "+_+") (pintype "passive"))
      (node (ref "F1") (pin "2") (pinfunction "2_2") (pintype "passive"))
      (node (ref "IC1") (pin "5") (pinfunction "VBUS_5") (pintype "bidirectional"))
      (node (ref "IC2") (pin "3") (pinfunction "IN_3") (pintype "input"))
    )
    (net (code "68") (name "VBUS_IN") (class "Default")
      (node (ref "F1") (pin "1") (pinfunction "1_1") (pintype "passive"))
      (node (ref "JP3") (pin "VBUS1") (pinfunction "VCC_VBUS1") (pintype "bidirectional"))
    )
    (net (code "69") (name "W5100_CS") (class "Default")
      (node (ref "IC6") (pin "29") (pinfunction "*SCS_29") (pintype "input"))
      (node (ref "R18") (pin "2") (pinfunction "2_2") (pintype "passive"))
      (node (ref "R2") (pin "1") (pinfunction "1_1") (pintype "passive"))
    )
    (net (code "70") (name "W5100_INT") (class "Default")
      (node (ref "IC6") (pin "56") (pinfunction "*INT_56") (pintype "input"))
      (node (ref "R13") (pin "1") (pinfunction "1_1") (pintype "passive"))
      (node (ref "U1") (pin "18") (pinfunction "PC2_18") (pintype "bidirectional"))
    )
    (net (code "71") (name "W5100_MISO") (class "Default")
      (node (ref "IC6") (pin "27") (pinfunction "MISO_27") (pintype "input"))
      (node (ref "U1") (pin "22") (pinfunction "PC6_22") (pintype "bidirectional"))
    )
    (net (code "72") (name "W5100_MOSI") (class "Default")
      (node (ref "IC6") (pin "28") (pinfunction "MOSI_28") (pintype "output"))
      (node (ref "R16") (pin "2") (pinfunction "2_2") (pintype "passive"))
    )
    (net (code "73") (name "W5100_RST") (class "Default")
      (node (ref "IC6") (pin "59") (pinfunction "*RESET_59") (pintype "input"))
      (node (ref "R14") (pin "1") (pinfunction "1_1") (pintype "passive"))
      (node (ref "U1") (pin "19") (pinfunction "PC3_19") (pintype "bidirectional"))
    )
    (net (code "74") (name "W5100_SCK") (class "Default")
      (node (ref "IC6") (pin "30") (pinfunction "SCLK_30") (pintype "input"))
      (node (ref "U1") (pin "21") (pinfunction "PC5_21") (pintype "bidirectional"))
    )
    (net (code "75") (name "XTLN") (class "Default")
      (node (ref "C16") (pin "2") (pinfunction "2_2") (pintype "passive"))
      (node (ref "IC6") (pin "75") (pinfunction "XTLN_75") (pintype "output"))
      (node (ref "R11") (pin "1") (pinfunction "1_1") (pintype "passive"))
      (node (ref "Y1") (pin "3") (pinfunction "1_3") (pintype "passive"))
    )
    (net (code "76") (name "XTLP") (class "Default")
      (node (ref "C15") (pin "2") (pinfunction "2_2") (pintype "passive"))
      (node (ref "IC6") (pin "76") (pinfunction "XTLP_76") (pintype "output"))
      (node (ref "R11") (pin "2") (pinfunction "2_2") (pintype "passive"))
      (node (ref "Y1") (pin "1") (pinfunction "2_1") (pintype "passive"))
    )
    (net (code "77") (name "unconnected-(IC6-COLLED-Pad71)") (class "Default")
      (node (ref "IC6") (pin "71") (pinfunction "COLLED_71") (pintype "output"))
    )
    (net (code "78") (name "unconnected-(IC6-D0-Pad26)") (class "Default")
      (node (ref "IC6") (pin "26") (pinfunction "D0_26") (pintype "input"))
    )
    (net (code "79") (name "unconnected-(IC6-D1-Pad25)") (class "Default")
      (node (ref "IC6") (pin "25") (pinfunction "D1_25") (pintype "input"))
    )
    (net (code "80") (name "unconnected-(IC6-D2-Pad24)") (class "Default")
      (node (ref "IC6") (pin "24") (pinfunction "D2_24") (pintype "input"))
    )
    (net (code "81") (name "unconnected-(IC6-D3-Pad23)") (class "Default")
      (node (ref "IC6") (pin "23") (pinfunction "D3_23") (pintype "input"))
    )
    (net (code "82") (name "unconnected-(IC6-D4-Pad22)") (class "Default")
      (node (ref "IC6") (pin "22") (pinfunction "D4_22") (pintype "input"))
    )
    (net (code "83") (name "unconnected-(IC6-D5-Pad21)") (class "Default")
      (node (ref "IC6") (pin "21") (pinfunction "D5_21") (pintype "input"))
    )
    (net (code "84") (name "unconnected-(IC6-D6-Pad20)") (class "Default")
      (node (ref "IC6") (pin "20") (pinfunction "D6_20") (pintype "input"))
    )
    (net (code "85") (name "unconnected-(IC6-D7-Pad19)") (class "Default")
      (node (ref "IC6") (pin "19") (pinfunction "D7_19") (pintype "input"))
    )
    (net (code "86") (name "unconnected-(IC6-NC-Pad3)") (class "Default")
      (node (ref "IC6") (pin "3") (pinfunction "NC_3") (pintype "no_connect"))
    )
    (net (code "87") (name "unconnected-(IC6-NC1-Pad60)") (class "Default")
      (node (ref "IC6") (pin "60") (pinfunction "NC1_60") (pintype "no_connect"))
    )
    (net (code "88") (name "unconnected-(IC6-NC2-Pad61)") (class "Default")
      (node (ref "IC6") (pin "61") (pinfunction "NC2_61") (pintype "no_connect"))
    )
    (net (code "89") (name "unconnected-(IC6-NC3-Pad62)") (class "Default")
      (node (ref "IC6") (pin "62") (pinfunction "NC3_62") (pintype "no_connect"))
    )
    (net (code "90") (name "unconnected-(IC6-NC4-Pad78)") (class "Default")
      (node (ref "IC6") (pin "78") (pinfunction "NC4_78") (pintype "no_connect"))
    )
    (net (code "91") (name "unconnected-(IC6-NC5-Pad79)") (class "Default")
      (node (ref "IC6") (pin "79") (pinfunction "NC5_79") (pintype "no_connect"))
    )
    (net (code "92") (name "unconnected-(IC6-NC6-Pad80)") (class "Default")
      (node (ref "IC6") (pin "80") (pinfunction "NC6_80") (pintype "no_connect"))
    )
    (net (code "93") (name "unconnected-(IC6-RXLED-Pad72)") (class "Default")
      (node (ref "IC6") (pin "72") (pinfunction "RXLED_72") (pintype "output"))
    )
    (net (code "94") (name "unconnected-(IC6-SPDLED-Pad67)") (class "Default")
      (node (ref "IC6") (pin "67") (pinfunction "SPDLED_67") (pintype "output"))
    )
    (net (code "95") (name "unconnected-(IC6-TXLED-Pad73)") (class "Default")
      (node (ref "IC6") (pin "73") (pinfunction "TXLED_73") (pintype "output"))
    )
    (net (code "96") (name "unconnected-(JP1-Pad3)") (class "Default")
      (node (ref "JP1") (pin "3") (pinfunction "3_3") (pintype "passive"))
    )
    (net (code "97") (name "unconnected-(JP1-Pad4)") (class "Default")
      (node (ref "JP1") (pin "4") (pinfunction "4_4") (pintype "passive"))
    )
    (net (code "98") (name "unconnected-(JP3-ID-PadID1)") (class "Default")
      (node (ref "JP3") (pin "ID1") (pinfunction "ID_ID1") (pintype "bidirectional"))
    )
    (net (code "99") (name "unconnected-(RJ1-PadNC)") (class "Default")
      (node (ref "RJ1") (pin "NC") (pinfunction "NC_NC") (pintype "bidirectional"))
    )
    (net (code "100") (name "unconnected-(U1-PD0-Pad26)") (class "Default")
      (node (ref "U1") (pin "26") (pinfunction "PD0_26") (pintype "bidirectional"))
    )
    (net (code "101") (name "unconnected-(U1-PD1-Pad27)") (class "Default")
      (node (ref "U1") (pin "27") (pinfunction "PD1_27") (pintype "bidirectional"))
    )
    (net (code "102") (name "unconnected-(U1-PD4-Pad30)") (class "Default")
      (node (ref "U1") (pin "30") (pinfunction "PD4_30") (pintype "bidirectional"))
    )
    (net (code "103") (name "unconnected-(U1-PD5-Pad31)") (class "Default")
      (node (ref "U1") (pin "31") (pinfunction "PD5_31") (pintype "bidirectional"))
    )
    (net (code "104") (name "unconnected-(U1-PE4-Pad40)") (class "Default")
      (node (ref "U1") (pin "40") (pinfunction "PE4_40") (pintype "bidirectional"))
    )
    (net (code "105") (name "unconnected-(U1-PF4-Pad50)") (class "Default")
      (node (ref "U1") (pin "50") (pinfunction "PF4_50") (pintype "bidirectional"))
    )
    (net (code "106") (name "unconnected-(U1-PF5-Pad51)") (class "Default")
      (node (ref "U1") (pin "51") (pinfunction "PF5_51") (pintype "bidirectional"))
    )
    (net (code "107") (name "unconnected-(U1-PF6-Pad54)") (class "Default")
      (node (ref "U1") (pin "54") (pinfunction "PF6_54") (pintype "bidirectional"))
    )
    (net (code "108") (name "unconnected-(U1-PF7-Pad55)") (class "Default")
      (node (ref "U1") (pin "55") (pinfunction "PF7_55") (pintype "bidirectional"))
    )
    (net (code "109") (name "unconnected-(U2-NC-Pad1)") (class "Default")
      (node (ref "U2") (pin "1") (pinfunction "NC_1") (pintype "bidirectional"))
    )
    (net (code "110") (name "unconnected-(U2-RSV-Pad8)") (class "Default")
      (node (ref "U2") (pin "8") (pinfunction "RSV_8") (pintype "bidirectional"))
    )
  )
)
